# USB-BOARD.net
KiCad netlist of a schematic drawn in EAGLE
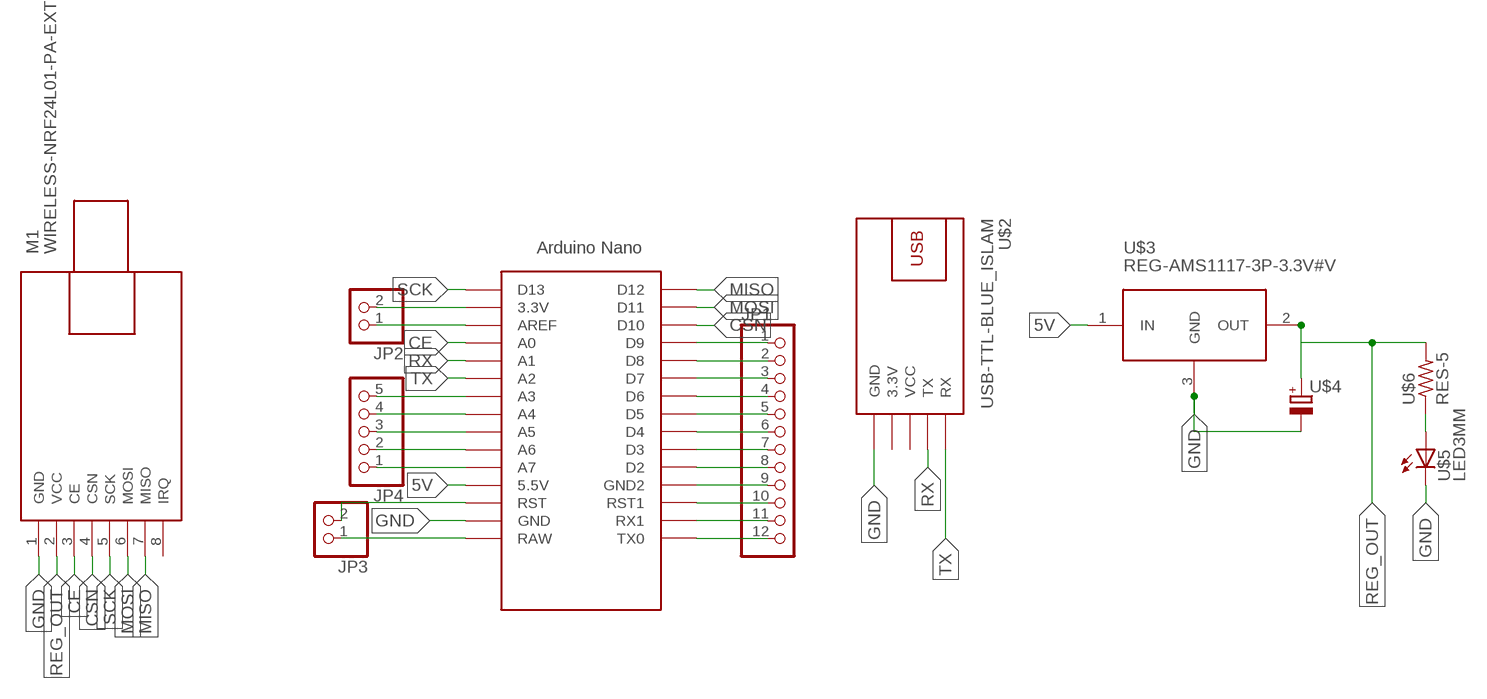
[diagram p0: schematic, sheet 1]

(export (version "E")
  (design (tool "Eeschema 10.0.6"))
  (components
    (comp (ref "JP1")
      (value "PINHD-1X12")
      (footprint "eagle-import:1X12")
      (libsource (lib "eagle-import") (part "PINHD-1X12"))
    )
    (comp (ref "JP2")
      (value "PINHD-1X2")
      (footprint "eagle-import:1X02")
      (libsource (lib "eagle-import") (part "PINHD-1X2"))
    )
    (comp (ref "JP3")
      (value "PINHD-1X2")
      (footprint "eagle-import:1X02")
      (libsource (lib "eagle-import") (part "PINHD-1X2"))
    )
    (comp (ref "JP4")
      (value "PINHD-1X5")
      (footprint "eagle-import:1X05")
      (libsource (lib "eagle-import") (part "PINHD-1X5"))
    )
    (comp (ref "M1")
      (value "WIRELESS-NRF24L01-PA-EXT")
      (footprint "eagle-import:WIRELESS-NRF24L01-PA-EXT")
      (libsource (lib "eagle-import") (part "WIRELESS-NRF24L01-PA-EXT"))
    )
    (comp (ref "U$1")
      (value "ARDUINO_NANO")
      (footprint "eagle-import:NANO")
      (libsource (lib "eagle-import") (part "ARDUINO_NANO"))
    )
    (comp (ref "U$2")
      (value "USB-TTL-BLUE_ISLAM")
      (footprint "eagle-import:USB-TTL-BLUE")
      (libsource (lib "eagle-import") (part "USB-TTL-BLUE_ISLAM"))
    )
    (comp (ref "U$3")
      (value "REG-AMS1117-3P-3.3V#V")
      (footprint "eagle-import:REG-AMS1117-3P#V")
      (libsource (lib "eagle-import") (part "REG-AMS1117-3P-#V3.3V"))
    )
    (comp (ref "U$4")
      (value "CAP_POL")
      (footprint "eagle-import:E3,5-8")
      (libsource (lib "eagle-import") (part "CAP_POL"))
    )
    (comp (ref "U$5")
      (value "LED3MM")
      (footprint "eagle-import:LED3MM")
      (libsource (lib "eagle-import") (part "LED3MM"))
    )
    (comp (ref "U$6")
      (value "RES-5")
      (footprint "eagle-import:0204_5")
      (libsource (lib "eagle-import") (part "RES-5"))
    )
  )
  (nets
    (net (code "1") (name "/VCC") (class "Default")
      (node (ref "U$2") (pin "VCC") (pinfunction "VCC_VCC") (pintype "power_in"))
    )
    (net (code "2") (name "5V") (class "Default")
      (node (ref "U$1") (pin "5V") (pinfunction "5.5V_5V") (pintype "bidirectional"))
      (node (ref "U$3") (pin "1") (pinfunction "IN_1") (pintype "bidirectional"))
    )
    (net (code "3") (name "CE") (class "Default")
      (node (ref "M1") (pin "3") (pinfunction "CE_3") (pintype "bidirectional"))
      (node (ref "U$1") (pin "A0") (pinfunction "A0_A0") (pintype "bidirectional"))
    )
    (net (code "4") (name "CSN") (class "Default")
      (node (ref "M1") (pin "4") (pinfunction "CSN_4") (pintype "bidirectional"))
      (node (ref "U$1") (pin "D10") (pinfunction "D10_D10") (pintype "bidirectional"))
    )
    (net (code "5") (name "GND") (class "Default")
      (node (ref "M1") (pin "1") (pinfunction "GND_1") (pintype "power_in"))
      (node (ref "U$1") (pin "GND") (pinfunction "GND_GND") (pintype "bidirectional"))
      (node (ref "U$2") (pin "GND") (pinfunction "GND_GND") (pintype "bidirectional"))
      (node (ref "U$3") (pin "3") (pinfunction "GND_3") (pintype "bidirectional"))
      (node (ref "U$4") (pin "-") (pinfunction "-_-") (pintype "passive"))
      (node (ref "U$5") (pin "K") (pinfunction "C_K") (pintype "passive"))
    )
    (net (code "6") (name "MISO") (class "Default")
      (node (ref "M1") (pin "7") (pinfunction "MISO_7") (pintype "bidirectional"))
      (node (ref "U$1") (pin "D12") (pinfunction "D12_D12") (pintype "bidirectional"))
    )
    (net (code "7") (name "MOSI") (class "Default")
      (node (ref "M1") (pin "6") (pinfunction "MOSI_6") (pintype "bidirectional"))
      (node (ref "U$1") (pin "D11") (pinfunction "D11_D11") (pintype "bidirectional"))
    )
    (net (code "8") (name "Net-(JP1-Pad1)") (class "Default")
      (node (ref "JP1") (pin "1") (pinfunction "1_1") (pintype "passive"))
      (node (ref "U$1") (pin "D9") (pinfunction "D9_D9") (pintype "bidirectional"))
    )
    (net (code "9") (name "Net-(JP1-Pad2)") (class "Default")
      (node (ref "JP1") (pin "2") (pinfunction "2_2") (pintype "passive"))
      (node (ref "U$1") (pin "D8") (pinfunction "D8_D8") (pintype "bidirectional"))
    )
    (net (code "10") (name "Net-(JP1-Pad3)") (class "Default")
      (node (ref "JP1") (pin "3") (pinfunction "3_3") (pintype "passive"))
      (node (ref "U$1") (pin "D7") (pinfunction "D7_D7") (pintype "bidirectional"))
    )
    (net (code "11") (name "Net-(JP1-Pad4)") (class "Default")
      (node (ref "JP1") (pin "4") (pinfunction "4_4") (pintype "passive"))
      (node (ref "U$1") (pin "D6") (pinfunction "D6_D6") (pintype "bidirectional"))
    )
    (net (code "12") (name "Net-(JP1-Pad5)") (class "Default")
      (node (ref "JP1") (pin "5") (pinfunction "5_5") (pintype "passive"))
      (node (ref "U$1") (pin "D5") (pinfunction "D5_D5") (pintype "bidirectional"))
    )
    (net (code "13") (name "Net-(JP1-Pad6)") (class "Default")
      (node (ref "JP1") (pin "6") (pinfunction "6_6") (pintype "passive"))
      (node (ref "U$1") (pin "D4") (pinfunction "D4_D4") (pintype "bidirectional"))
    )
    (net (code "14") (name "Net-(JP1-Pad7)") (class "Default")
      (node (ref "JP1") (pin "7") (pinfunction "7_7") (pintype "passive"))
      (node (ref "U$1") (pin "D3") (pinfunction "D3_D3") (pintype "bidirectional"))
    )
    (net (code "15") (name "Net-(JP1-Pad8)") (class "Default")
      (node (ref "JP1") (pin "8") (pinfunction "8_8") (pintype "passive"))
      (node (ref "U$1") (pin "D2") (pinfunction "D2_D2") (pintype "bidirectional"))
    )
    (net (code "16") (name "Net-(JP1-Pad10)") (class "Default")
      (node (ref "JP1") (pin "10") (pinfunction "10_10") (pintype "passive"))
      (node (ref "U$1") (pin "RST1") (pinfunction "RST1_RST1") (pintype "bidirectional"))
    )
    (net (code "17") (name "Net-(JP1-Pad11)") (class "Default")
      (node (ref "JP1") (pin "11") (pinfunction "11_11") (pintype "passive"))
      (node (ref "U$1") (pin "RX1") (pinfunction "RX1_RX1") (pintype "bidirectional"))
    )
    (net (code "18") (name "Net-(JP1-Pad12)") (class "Default")
      (node (ref "JP1") (pin "12") (pinfunction "12_12") (pintype "passive"))
      (node (ref "U$1") (pin "TX0") (pinfunction "TX0_TX0") (pintype "bidirectional"))
    )
    (net (code "19") (name "Net-(JP2-Pad1)") (class "Default")
      (node (ref "JP2") (pin "1") (pinfunction "1_1") (pintype "passive"))
      (node (ref "U$1") (pin "AREF") (pinfunction "AREF_AREF") (pintype "bidirectional"))
    )
    (net (code "20") (name "Net-(JP2-Pad2)") (class "Default")
      (node (ref "JP2") (pin "2") (pinfunction "2_2") (pintype "passive"))
      (node (ref "U$1") (pin "3.3V") (pinfunction "3.3V_3.3V") (pintype "bidirectional"))
    )
    (net (code "21") (name "Net-(JP3-Pad1)") (class "Default")
      (node (ref "JP3") (pin "1") (pinfunction "1_1") (pintype "passive"))
      (node (ref "U$1") (pin "RAW") (pinfunction "RAW_RAW") (pintype "bidirectional"))
    )
    (net (code "22") (name "Net-(JP3-Pad2)") (class "Default")
      (node (ref "JP3") (pin "2") (pinfunction "2_2") (pintype "passive"))
      (node (ref "U$1") (pin "RST") (pinfunction "RST_RST") (pintype "bidirectional"))
    )
    (net (code "23") (name "Net-(JP4-Pad1)") (class "Default")
      (node (ref "JP4") (pin "1") (pinfunction "1_1") (pintype "passive"))
      (node (ref "U$1") (pin "A7") (pinfunction "A7_A7") (pintype "bidirectional"))
    )
    (net (code "24") (name "Net-(JP4-Pad2)") (class "Default")
      (node (ref "JP4") (pin "2") (pinfunction "2_2") (pintype "passive"))
      (node (ref "U$1") (pin "A6") (pinfunction "A6_A6") (pintype "bidirectional"))
    )
    (net (code "25") (name "Net-(JP4-Pad3)") (class "Default")
      (node (ref "JP4") (pin "3") (pinfunction "3_3") (pintype "passive"))
      (node (ref "U$1") (pin "A5") (pinfunction "A5_A5") (pintype "bidirectional"))
    )
    (net (code "26") (name "Net-(JP4-Pad4)") (class "Default")
      (node (ref "JP4") (pin "4") (pinfunction "4_4") (pintype "passive"))
      (node (ref "U$1") (pin "A4") (pinfunction "A4_A4") (pintype "bidirectional"))
    )
    (net (code "27") (name "Net-(JP4-Pad5)") (class "Default")
      (node (ref "JP4") (pin "5") (pinfunction "5_5") (pintype "passive"))
      (node (ref "U$1") (pin "A3") (pinfunction "A3_A3") (pintype "bidirectional"))
    )
    (net (code "28") (name "Net-(U$1-GND2)") (class "Default")
      (node (ref "JP1") (pin "9") (pinfunction "9_9") (pintype "passive"))
      (node (ref "U$1") (pin "GND1") (pinfunction "GND2_GND1") (pintype "bidirectional"))
    )
    (net (code "29") (name "Net-(U$5-PadA)") (class "Default")
      (node (ref "U$5") (pin "A") (pinfunction "A_A") (pintype "passive"))
      (node (ref "U$6") (pin "1") (pinfunction "1_1") (pintype "passive"))
    )
    (net (code "30") (name "REG_OUT") (class "Default")
      (node (ref "M1") (pin "2") (pinfunction "VCC_2") (pintype "power_in"))
      (node (ref "U$3") (pin "2") (pinfunction "OUT_2") (pintype "bidirectional"))
      (node (ref "U$4") (pin "+") (pinfunction "+_+") (pintype "passive"))
      (node (ref "U$6") (pin "2") (pinfunction "2_2") (pintype "passive"))
    )
    (net (code "31") (name "RX") (class "Default")
      (node (ref "U$1") (pin "A1") (pinfunction "A1_A1") (pintype "bidirectional"))
      (node (ref "U$2") (pin "TX") (pinfunction "TX_TX") (pintype "bidirectional"))
    )
    (net (code "32") (name "SCK") (class "Default")
      (node (ref "M1") (pin "5") (pinfunction "SCK_5") (pintype "bidirectional"))
      (node (ref "U$1") (pin "D13") (pinfunction "D13_D13") (pintype "bidirectional"))
    )
    (net (code "33") (name "TX") (class "Default")
      (node (ref "U$1") (pin "A2") (pinfunction "A2_A2") (pintype "bidirectional"))
      (node (ref "U$2") (pin "RX") (pinfunction "RX_RX") (pintype "bidirectional"))
    )
    (net (code "34") (name "unconnected-(M1-IRQ-Pad8)") (class "Default")
      (node (ref "M1") (pin "8") (pinfunction "IRQ_8") (pintype "bidirectional"))
    )
    (net (code "35") (name "unconnected-(U$2-Pad3.3V)") (class "Default")
      (node (ref "U$2") (pin "3.3V") (pinfunction "3.3V_3.3V") (pintype "bidirectional"))
    )
  )
)
